# PowerScope_004.net
KiCad netlist of a schematic drawn in EAGLE
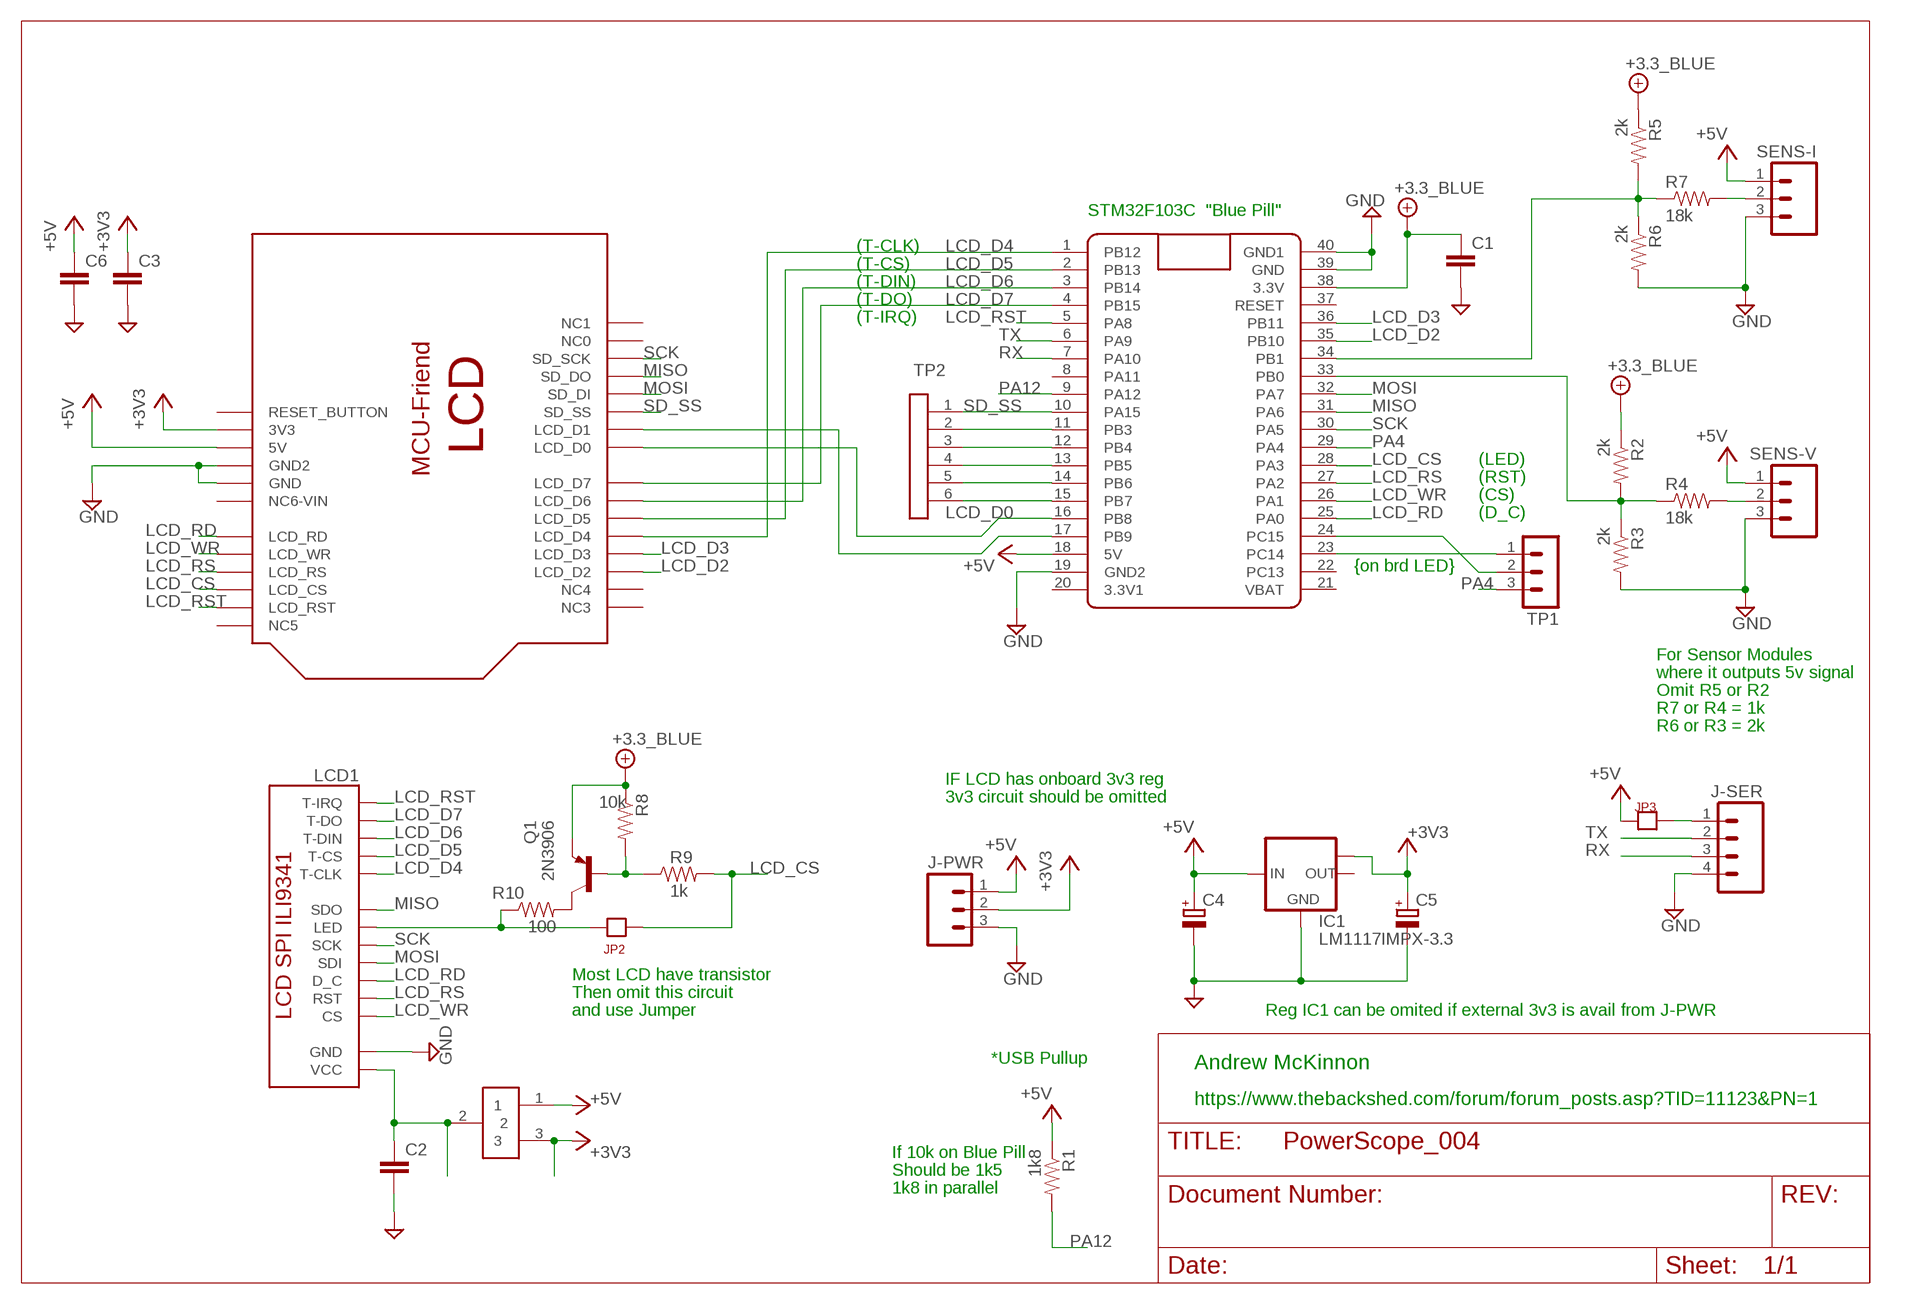
[diagram p0: schematic, sheet 1]

(export (version "E")
  (design (tool "Eeschema 10.0.6"))
  (components
    (comp (ref "C1")
      (value "BCAP")
      (footprint "eagle-import:BCAP")
      (libsource (lib "eagle-import") (part "BCAP"))
    )
    (comp (ref "C2")
      (value "BCAP")
      (footprint "eagle-import:BCAP")
      (libsource (lib "eagle-import") (part "BCAP"))
    )
    (comp (ref "C3")
      (value "BCAP")
      (footprint "eagle-import:BCAP")
      (libsource (lib "eagle-import") (part "BCAP"))
    )
    (comp (ref "C4")
      (value "C-RB200100")
      (footprint "eagle-import:CPOL-RADIAL-10UF-25V")
      (libsource (lib "eagle-import") (part "C-RB200100"))
    )
    (comp (ref "C5")
      (value "C-RB200100")
      (footprint "eagle-import:CPOL-RADIAL-10UF-25V")
      (libsource (lib "eagle-import") (part "C-RB200100"))
    )
    (comp (ref "C6")
      (value "BCAP")
      (footprint "eagle-import:BCAP")
      (libsource (lib "eagle-import") (part "BCAP"))
    )
    (comp (ref "IC1")
      (value "LM1117IMPX-3.3")
      (footprint "eagle-import:SOT223")
      (libsource (lib "eagle-import") (part "LM1117IMPX-3.3"))
    )
    (comp (ref "J-PWR")
      (value "MO3POL")
      (footprint "eagle-import:MOLEX-3")
      (libsource (lib "eagle-import") (part "MO3POL"))
    )
    (comp (ref "J-SER")
      (value "MO4POL")
      (footprint "eagle-import:MOLEX-4")
      (libsource (lib "eagle-import") (part "MO4POL"))
    )
    (comp (ref "JP1")
      (value "JP1X3")
      (footprint "eagle-import:JP1X3")
      (libsource (lib "eagle-import") (part "JP1X3"))
    )
    (comp (ref "JP2")
      (value "JP1")
      (footprint "eagle-import:JP1")
      (libsource (lib "eagle-import") (part "JP1"))
    )
    (comp (ref "JP3")
      (value "JP1")
      (footprint "eagle-import:JP1")
      (libsource (lib "eagle-import") (part "JP1"))
    )
    (comp (ref "LCD1")
      (value "LCD_ILI9341_SPI_TREV")
      (footprint "eagle-import:LCD_ILI9341_SPI_24T_REVERSE")
      (libsource (lib "eagle-import") (part "LCD_ILI9341_SPI_TREV"))
    )
    (comp (ref "Q1")
      (value "2N3906")
      (footprint "eagle-import:TO92")
      (libsource (lib "eagle-import") (part "2N3906"))
    )
    (comp (ref "R1")
      (value "1k8")
      (footprint "eagle-import:R4_SP")
      (libsource (lib "eagle-import") (part "R4SMALLPAD"))
    )
    (comp (ref "R2")
      (value "2k")
      (footprint "eagle-import:R4_SP")
      (libsource (lib "eagle-import") (part "R4SMALLPAD"))
    )
    (comp (ref "R3")
      (value "2k")
      (footprint "eagle-import:R4_SP")
      (libsource (lib "eagle-import") (part "R4SMALLPAD"))
    )
    (comp (ref "R4")
      (value "18k")
      (footprint "eagle-import:R4_SP")
      (libsource (lib "eagle-import") (part "R4SMALLPAD"))
    )
    (comp (ref "R5")
      (value "2k")
      (footprint "eagle-import:R4_SP")
      (libsource (lib "eagle-import") (part "R4SMALLPAD"))
    )
    (comp (ref "R6")
      (value "2k")
      (footprint "eagle-import:R4_SP")
      (libsource (lib "eagle-import") (part "R4SMALLPAD"))
    )
    (comp (ref "R7")
      (value "18k")
      (footprint "eagle-import:R4_SP")
      (libsource (lib "eagle-import") (part "R4SMALLPAD"))
    )
    (comp (ref "R8")
      (value "10k")
      (footprint "eagle-import:R4_SP")
      (libsource (lib "eagle-import") (part "R4SMALLPAD"))
    )
    (comp (ref "R9")
      (value "1k")
      (footprint "eagle-import:R4_SP")
      (libsource (lib "eagle-import") (part "R4SMALLPAD"))
    )
    (comp (ref "R10")
      (value "100")
      (footprint "eagle-import:R4_SP")
      (libsource (lib "eagle-import") (part "R4SMALLPAD"))
    )
    (comp (ref "SENS-I")
      (value "MO3POL")
      (footprint "eagle-import:MOLEX-3")
      (libsource (lib "eagle-import") (part "MO3POL"))
    )
    (comp (ref "SENS-V")
      (value "MO3POL")
      (footprint "eagle-import:MOLEX-3")
      (libsource (lib "eagle-import") (part "MO3POL"))
    )
    (comp (ref "TP1")
      (value "MA03-1")
      (footprint "eagle-import:MA03-1")
      (libsource (lib "eagle-import") (part "MA03-1"))
    )
    (comp (ref "TP2")
      (value "SIL-6")
      (footprint "eagle-import:SIL6")
      (libsource (lib "eagle-import") (part "SIL-6"))
    )
    (comp (ref "U$2")
      (value "LCD_MCUFRIENDREV")
      (footprint "eagle-import:LCD-MCUFRIEND-24T-REV")
      (libsource (lib "eagle-import") (part "LCD_MCUFRIENDREV"))
    )
    (comp (ref "U$3")
      (value "BLUE_PILL")
      (footprint "eagle-import:BLUE_PILL_CLEAN")
      (libsource (lib "eagle-import") (part "BLUE_PILL"))
    )
  )
  (nets
    (net (code "1") (name "+3.3_BLUE") (class "Default")
      (node (ref "C1") (pin "1") (pinfunction "1_1") (pintype "passive"))
      (node (ref "Q1") (pin "3") (pinfunction "E_3") (pintype "passive"))
      (node (ref "R2") (pin "P$1") (pinfunction "1_P$1") (pintype "passive"))
      (node (ref "R5") (pin "P$1") (pinfunction "1_P$1") (pintype "passive"))
      (node (ref "R8") (pin "P$1") (pinfunction "1_P$1") (pintype "passive"))
      (node (ref "U$3") (pin "38") (pinfunction "3.3V_38") (pintype "bidirectional"))
    )
    (net (code "2") (name "+3V3") (class "Default")
      (node (ref "C3") (pin "1") (pinfunction "1_1") (pintype "passive"))
      (node (ref "C5") (pin "1") (pinfunction "+_1") (pintype "passive"))
      (node (ref "IC1") (pin "TAB") (pinfunction "OUT1_TAB") (pintype "passive"))
      (node (ref "J-PWR") (pin "2") (pinfunction "2_2") (pintype "passive"))
      (node (ref "JP1") (pin "3") (pinfunction "3_3") (pintype "bidirectional"))
      (node (ref "U$2") (pin "3V") (pinfunction "3V3_3V") (pintype "power_in"))
    )
    (net (code "3") (name "+5V") (class "Default")
      (node (ref "C4") (pin "1") (pinfunction "+_1") (pintype "passive"))
      (node (ref "C6") (pin "1") (pinfunction "1_1") (pintype "passive"))
      (node (ref "IC1") (pin "3") (pinfunction "IN_3") (pintype "input"))
      (node (ref "J-PWR") (pin "1") (pinfunction "1_1") (pintype "passive"))
      (node (ref "JP1") (pin "1") (pinfunction "1_1") (pintype "bidirectional"))
      (node (ref "JP3") (pin "1") (pinfunction "1_1") (pintype "bidirectional"))
      (node (ref "R1") (pin "P$1") (pinfunction "1_P$1") (pintype "passive"))
      (node (ref "SENS-I") (pin "1") (pinfunction "1_1") (pintype "passive"))
      (node (ref "SENS-V") (pin "1") (pinfunction "1_1") (pintype "passive"))
      (node (ref "U$2") (pin "5V") (pinfunction "5V_5V") (pintype "power_in"))
      (node (ref "U$3") (pin "18") (pinfunction "5V_18") (pintype "bidirectional"))
    )
    (net (code "4") (name "/LCD_CS") (class "Default")
      (node (ref "JP2") (pin "2") (pinfunction "2_2") (pintype "bidirectional"))
      (node (ref "R9") (pin "P$2") (pinfunction "2_P$2") (pintype "passive"))
      (node (ref "U$2") (pin "LCD_CS") (pinfunction "LCD_CS_LCD_CS") (pintype "bidirectional"))
      (node (ref "U$3") (pin "28") (pinfunction "PA3_28") (pintype "bidirectional"))
    )
    (net (code "5") (name "/LCD_D0") (class "Default")
      (node (ref "U$2") (pin "LCD_D0") (pinfunction "LCD_D0_LCD_D0") (pintype "bidirectional"))
      (node (ref "U$3") (pin "16") (pinfunction "PB8_16") (pintype "bidirectional"))
    )
    (net (code "6") (name "/LCD_D2") (class "Default")
      (node (ref "U$2") (pin "LCD_D2") (pinfunction "LCD_D2_LCD_D2") (pintype "bidirectional"))
      (node (ref "U$3") (pin "35") (pinfunction "PB10_35") (pintype "bidirectional"))
    )
    (net (code "7") (name "/LCD_D3") (class "Default")
      (node (ref "U$2") (pin "LCD_D3") (pinfunction "LCD_D3_LCD_D3") (pintype "bidirectional"))
      (node (ref "U$3") (pin "36") (pinfunction "PB11_36") (pintype "bidirectional"))
    )
    (net (code "8") (name "/LCD_D4") (class "Default")
      (node (ref "LCD1") (pin "T_CLK") (pinfunction "T-CLK_T_CLK") (pintype "input"))
      (node (ref "U$2") (pin "LCD_D4") (pinfunction "LCD_D4_LCD_D4") (pintype "bidirectional"))
      (node (ref "U$3") (pin "1") (pinfunction "PB12_1") (pintype "bidirectional"))
    )
    (net (code "9") (name "/LCD_D5") (class "Default")
      (node (ref "LCD1") (pin "T_CS") (pinfunction "T-CS_T_CS") (pintype "input"))
      (node (ref "U$2") (pin "LCD_D5") (pinfunction "LCD_D5_LCD_D5") (pintype "bidirectional"))
      (node (ref "U$3") (pin "2") (pinfunction "PB13_2") (pintype "bidirectional"))
    )
    (net (code "10") (name "/LCD_D6") (class "Default")
      (node (ref "LCD1") (pin "T_DI") (pinfunction "T-DIN_T_DI") (pintype "input"))
      (node (ref "U$2") (pin "LCD_D6") (pinfunction "LCD_D6_LCD_D6") (pintype "bidirectional"))
      (node (ref "U$3") (pin "3") (pinfunction "PB14_3") (pintype "bidirectional"))
    )
    (net (code "11") (name "/LCD_D7") (class "Default")
      (node (ref "LCD1") (pin "T_DO") (pinfunction "T-DO_T_DO") (pintype "bidirectional"))
      (node (ref "U$2") (pin "LCD_D7") (pinfunction "LCD_D7_LCD_D7") (pintype "bidirectional"))
      (node (ref "U$3") (pin "4") (pinfunction "PB15_4") (pintype "bidirectional"))
    )
    (net (code "12") (name "/LCD_RD") (class "Default")
      (node (ref "LCD1") (pin "D_C") (pinfunction "D_C_D_C") (pintype "bidirectional"))
      (node (ref "U$2") (pin "LCD_RD") (pinfunction "LCD_RD_LCD_RD") (pintype "bidirectional"))
      (node (ref "U$3") (pin "25") (pinfunction "PA0_25") (pintype "bidirectional"))
    )
    (net (code "13") (name "/LCD_RS") (class "Default")
      (node (ref "LCD1") (pin "RST") (pinfunction "RST_RST") (pintype "bidirectional"))
      (node (ref "U$2") (pin "LCD_RS") (pinfunction "LCD_RS_LCD_RS") (pintype "bidirectional"))
      (node (ref "U$3") (pin "27") (pinfunction "PA2_27") (pintype "bidirectional"))
    )
    (net (code "14") (name "/LCD_RST") (class "Default")
      (node (ref "LCD1") (pin "T-IRQ") (pinfunction "T-IRQ_T-IRQ") (pintype "bidirectional"))
      (node (ref "U$2") (pin "LCD_RST") (pinfunction "LCD_RST_LCD_RST") (pintype "bidirectional"))
      (node (ref "U$3") (pin "5") (pinfunction "PA8_5") (pintype "bidirectional"))
    )
    (net (code "15") (name "/LCD_WR") (class "Default")
      (node (ref "LCD1") (pin "CS") (pinfunction "CS_CS") (pintype "bidirectional"))
      (node (ref "U$2") (pin "LCD_WR") (pinfunction "LCD_WR_LCD_WR") (pintype "bidirectional"))
      (node (ref "U$3") (pin "26") (pinfunction "PA1_26") (pintype "bidirectional"))
    )
    (net (code "16") (name "/MISO") (class "Default")
      (node (ref "LCD1") (pin "SDO") (pinfunction "SDO_SDO") (pintype "bidirectional"))
      (node (ref "U$2") (pin "SD_DO") (pinfunction "SD_DO_SD_DO") (pintype "bidirectional"))
      (node (ref "U$3") (pin "31") (pinfunction "PA6_31") (pintype "bidirectional"))
    )
    (net (code "17") (name "/MOSI") (class "Default")
      (node (ref "LCD1") (pin "SDI") (pinfunction "SDI_SDI") (pintype "bidirectional"))
      (node (ref "U$2") (pin "SD_DI") (pinfunction "SD_DI_SD_DI") (pintype "bidirectional"))
      (node (ref "U$3") (pin "32") (pinfunction "PA7_32") (pintype "bidirectional"))
    )
    (net (code "18") (name "/PA4") (class "Default")
      (node (ref "TP1") (pin "3") (pinfunction "3_3") (pintype "passive"))
      (node (ref "U$3") (pin "29") (pinfunction "PA4_29") (pintype "bidirectional"))
    )
    (net (code "19") (name "/PA12") (class "Default")
      (node (ref "R1") (pin "P$2") (pinfunction "2_P$2") (pintype "passive"))
      (node (ref "U$3") (pin "9") (pinfunction "PA12_9") (pintype "bidirectional"))
    )
    (net (code "20") (name "/RX") (class "Default")
      (node (ref "J-SER") (pin "3") (pinfunction "3_3") (pintype "passive"))
      (node (ref "U$3") (pin "7") (pinfunction "PA10_7") (pintype "bidirectional"))
    )
    (net (code "21") (name "/SCK") (class "Default")
      (node (ref "LCD1") (pin "SCK") (pinfunction "SCK_SCK") (pintype "bidirectional"))
      (node (ref "U$2") (pin "SD_SCK") (pinfunction "SD_SCK_SD_SCK") (pintype "bidirectional"))
      (node (ref "U$3") (pin "30") (pinfunction "PA5_30") (pintype "bidirectional"))
    )
    (net (code "22") (name "/SD_SS") (class "Default")
      (node (ref "TP2") (pin "1") (pinfunction "P$1_1") (pintype "bidirectional"))
      (node (ref "U$2") (pin "SD_SS") (pinfunction "SD_SS_SD_SS") (pintype "bidirectional"))
      (node (ref "U$3") (pin "10") (pinfunction "PA15_10") (pintype "bidirectional"))
    )
    (net (code "23") (name "/TX") (class "Default")
      (node (ref "J-SER") (pin "2") (pinfunction "2_2") (pintype "passive"))
      (node (ref "U$3") (pin "6") (pinfunction "PA9_6") (pintype "bidirectional"))
    )
    (net (code "24") (name "GND") (class "Default")
      (node (ref "C1") (pin "2") (pinfunction "2_2") (pintype "passive"))
      (node (ref "C2") (pin "2") (pinfunction "2_2") (pintype "passive"))
      (node (ref "C3") (pin "2") (pinfunction "2_2") (pintype "passive"))
      (node (ref "C4") (pin "2") (pinfunction "-_2") (pintype "passive"))
      (node (ref "C5") (pin "2") (pinfunction "-_2") (pintype "passive"))
      (node (ref "C6") (pin "2") (pinfunction "2_2") (pintype "passive"))
      (node (ref "IC1") (pin "1") (pinfunction "GND_1") (pintype "input"))
      (node (ref "J-PWR") (pin "3") (pinfunction "3_3") (pintype "passive"))
      (node (ref "J-SER") (pin "4") (pinfunction "4_4") (pintype "passive"))
      (node (ref "LCD1") (pin "GND") (pinfunction "GND_GND") (pintype "power_in"))
      (node (ref "R3") (pin "P$2") (pinfunction "2_P$2") (pintype "passive"))
      (node (ref "R6") (pin "P$2") (pinfunction "2_P$2") (pintype "passive"))
      (node (ref "SENS-I") (pin "3") (pinfunction "3_3") (pintype "passive"))
      (node (ref "SENS-V") (pin "3") (pinfunction "3_3") (pintype "passive"))
      (node (ref "U$2") (pin "GND") (pinfunction "GND_GND") (pintype "power_in"))
      (node (ref "U$2") (pin "GND2") (pinfunction "GND2_GND2") (pintype "power_in"))
      (node (ref "U$3") (pin "19") (pinfunction "GND2_19") (pintype "bidirectional"))
      (node (ref "U$3") (pin "39") (pinfunction "GND_39") (pintype "bidirectional"))
      (node (ref "U$3") (pin "40") (pinfunction "GND1_40") (pintype "power_in"))
    )
    (net (code "25") (name "Net-(C2-Pad1)") (class "Default")
      (node (ref "C2") (pin "1") (pinfunction "1_1") (pintype "passive"))
      (node (ref "JP1") (pin "2") (pinfunction "2_2") (pintype "bidirectional"))
      (node (ref "LCD1") (pin "VCC") (pinfunction "VCC_VCC") (pintype "power_in"))
    )
    (net (code "26") (name "Net-(J-SER-Pad1)") (class "Default")
      (node (ref "J-SER") (pin "1") (pinfunction "1_1") (pintype "passive"))
      (node (ref "JP3") (pin "2") (pinfunction "2_2") (pintype "bidirectional"))
    )
    (net (code "27") (name "Net-(Q1-B)") (class "Default")
      (node (ref "Q1") (pin "2") (pinfunction "B_2") (pintype "passive"))
      (node (ref "R8") (pin "P$2") (pinfunction "2_P$2") (pintype "passive"))
      (node (ref "R9") (pin "P$1") (pinfunction "1_P$1") (pintype "passive"))
    )
    (net (code "28") (name "Net-(Q1-C)") (class "Default")
      (node (ref "Q1") (pin "1") (pinfunction "C_1") (pintype "passive"))
      (node (ref "R10") (pin "P$2") (pinfunction "2_P$2") (pintype "passive"))
    )
    (net (code "29") (name "Net-(R2-2)") (class "Default")
      (node (ref "R2") (pin "P$2") (pinfunction "2_P$2") (pintype "passive"))
      (node (ref "R3") (pin "P$1") (pinfunction "1_P$1") (pintype "passive"))
      (node (ref "R4") (pin "P$1") (pinfunction "1_P$1") (pintype "passive"))
      (node (ref "U$3") (pin "33") (pinfunction "PB0_33") (pintype "bidirectional"))
    )
    (net (code "30") (name "Net-(R4-2)") (class "Default")
      (node (ref "R4") (pin "P$2") (pinfunction "2_P$2") (pintype "passive"))
      (node (ref "SENS-V") (pin "2") (pinfunction "2_2") (pintype "passive"))
    )
    (net (code "31") (name "Net-(R5-2)") (class "Default")
      (node (ref "R5") (pin "P$2") (pinfunction "2_P$2") (pintype "passive"))
      (node (ref "R6") (pin "P$1") (pinfunction "1_P$1") (pintype "passive"))
      (node (ref "R7") (pin "P$1") (pinfunction "1_P$1") (pintype "passive"))
      (node (ref "U$3") (pin "34") (pinfunction "PB1_34") (pintype "bidirectional"))
    )
    (net (code "32") (name "Net-(R7-2)") (class "Default")
      (node (ref "R7") (pin "P$2") (pinfunction "2_P$2") (pintype "passive"))
      (node (ref "SENS-I") (pin "2") (pinfunction "2_2") (pintype "passive"))
    )
    (net (code "33") (name "Net-(R10-1)") (class "Default")
      (node (ref "JP2") (pin "1") (pinfunction "1_1") (pintype "bidirectional"))
      (node (ref "LCD1") (pin "LED") (pinfunction "LED_LED") (pintype "bidirectional"))
      (node (ref "R10") (pin "P$1") (pinfunction "1_P$1") (pintype "passive"))
    )
    (net (code "34") (name "Net-(TP2-P$2)") (class "Default")
      (node (ref "TP2") (pin "2") (pinfunction "P$2_2") (pintype "bidirectional"))
      (node (ref "U$3") (pin "11") (pinfunction "PB3_11") (pintype "bidirectional"))
    )
    (net (code "35") (name "Net-(TP2-P$3)") (class "Default")
      (node (ref "TP2") (pin "3") (pinfunction "P$3_3") (pintype "bidirectional"))
      (node (ref "U$3") (pin "12") (pinfunction "PB4_12") (pintype "bidirectional"))
    )
    (net (code "36") (name "Net-(TP2-P$4)") (class "Default")
      (node (ref "TP2") (pin "4") (pinfunction "P$4_4") (pintype "bidirectional"))
      (node (ref "U$3") (pin "13") (pinfunction "PB5_13") (pintype "bidirectional"))
    )
    (net (code "37") (name "Net-(TP2-P$5)") (class "Default")
      (node (ref "TP2") (pin "5") (pinfunction "P$5_5") (pintype "bidirectional"))
      (node (ref "U$3") (pin "14") (pinfunction "PB6_14") (pintype "bidirectional"))
    )
    (net (code "38") (name "Net-(TP2-P$6)") (class "Default")
      (node (ref "TP2") (pin "6") (pinfunction "P$6_6") (pintype "bidirectional"))
      (node (ref "U$3") (pin "15") (pinfunction "PB7_15") (pintype "bidirectional"))
    )
    (net (code "39") (name "Net-(U$3-PB9)") (class "Default")
      (node (ref "U$2") (pin "LCD_D1") (pinfunction "LCD_D1_LCD_D1") (pintype "bidirectional"))
      (node (ref "U$3") (pin "17") (pinfunction "PB9_17") (pintype "bidirectional"))
    )
    (net (code "40") (name "Net-(U$3-PC14)") (class "Default")
      (node (ref "TP1") (pin "1") (pinfunction "1_1") (pintype "passive"))
      (node (ref "U$3") (pin "23") (pinfunction "PC14_23") (pintype "bidirectional"))
    )
    (net (code "41") (name "Net-(U$3-PC15)") (class "Default")
      (node (ref "TP1") (pin "2") (pinfunction "2_2") (pintype "passive"))
      (node (ref "U$3") (pin "24") (pinfunction "PC15_24") (pintype "bidirectional"))
    )
    (net (code "42") (name "unconnected-(IC1-OUT-Pad2)") (class "Default")
      (node (ref "IC1") (pin "2") (pinfunction "OUT_2") (pintype "passive"))
    )
    (net (code "43") (name "unconnected-(U$2-NC1-PadNC2)") (class "Default")
      (node (ref "U$2") (pin "NC2") (pinfunction "NC1_NC2") (pintype "no_connect"))
    )
    (net (code "44") (name "unconnected-(U$2-NC6-VIN-PadVIN)") (class "Default")
      (node (ref "U$2") (pin "VIN") (pinfunction "NC6-VIN_VIN") (pintype "no_connect"))
    )
    (net (code "45") (name "unconnected-(U$2-PadNC0)") (class "Default")
      (node (ref "U$2") (pin "NC0") (pinfunction "NC0_NC0") (pintype "no_connect"))
    )
    (net (code "46") (name "unconnected-(U$2-PadNC3)") (class "Default")
      (node (ref "U$2") (pin "NC3") (pinfunction "NC3_NC3") (pintype "no_connect"))
    )
    (net (code "47") (name "unconnected-(U$2-PadNC4)") (class "Default")
      (node (ref "U$2") (pin "NC4") (pinfunction "NC4_NC4") (pintype "no_connect"))
    )
    (net (code "48") (name "unconnected-(U$2-PadNC5)") (class "Default")
      (node (ref "U$2") (pin "NC5") (pinfunction "NC5_NC5") (pintype "no_connect"))
    )
    (net (code "49") (name "unconnected-(U$2-PadRESET_BUTTON)") (class "Default")
      (node (ref "U$2") (pin "RESET_BUTTON") (pinfunction "RESET_BUTTON_RESET_BUTTON") (pintype "bidirectional"))
    )
    (net (code "50") (name "unconnected-(U$3-3.3V1-Pad20)") (class "Default")
      (node (ref "U$3") (pin "20") (pinfunction "3.3V1_20") (pintype "bidirectional"))
    )
    (net (code "51") (name "unconnected-(U$3-PA11-Pad8)") (class "Default")
      (node (ref "U$3") (pin "8") (pinfunction "PA11_8") (pintype "bidirectional"))
    )
    (net (code "52") (name "unconnected-(U$3-PC13-Pad22)") (class "Default")
      (node (ref "U$3") (pin "22") (pinfunction "PC13_22") (pintype "bidirectional"))
    )
    (net (code "53") (name "unconnected-(U$3-RESET-Pad37)") (class "Default")
      (node (ref "U$3") (pin "37") (pinfunction "RESET_37") (pintype "bidirectional"))
    )
    (net (code "54") (name "unconnected-(U$3-VBAT-Pad21)") (class "Default")
      (node (ref "U$3") (pin "21") (pinfunction "VBAT_21") (pintype "bidirectional"))
    )
  )
)
